# RSD_M1_LED_TURN_LEFT_V2.net
KiCad netlist of a schematic drawn in Altium Designer
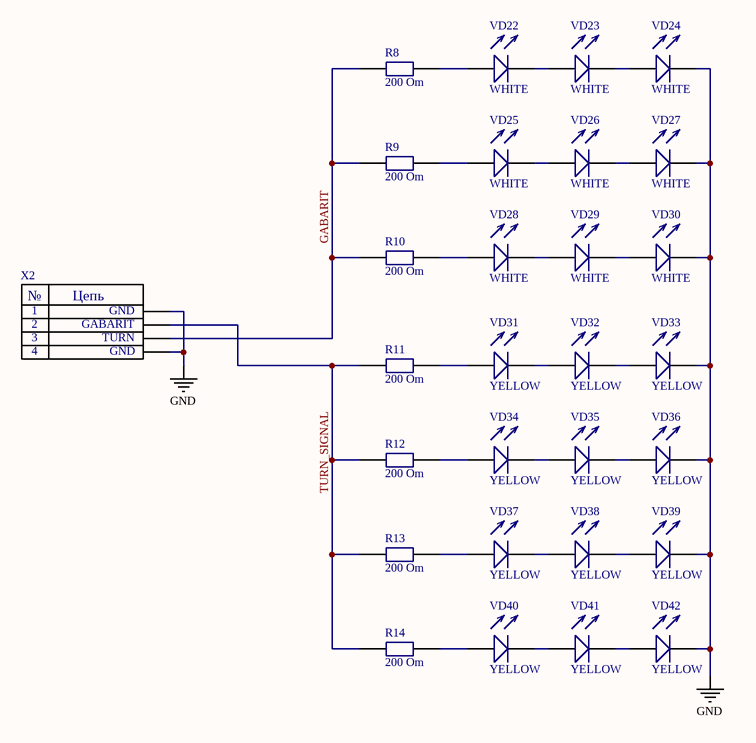
[diagram p0: RSD_M1_LED_TURN_LEFT_V2.SchDoc]

(export (version "E")
  (design (tool "Eeschema 10.0.6"))
  (components
    (comp (ref "R8")
      (value "200 Om")
      (footprint "Res0603")
      (fields (field (name "Comment") "Resistor"))
      (libsource (lib "my_library") (part "Resistor"))
    )
    (comp (ref "R9")
      (value "200 Om")
      (footprint "Res0603")
      (fields (field (name "Comment") "Resistor"))
      (libsource (lib "my_library") (part "Resistor"))
    )
    (comp (ref "R10")
      (value "200 Om")
      (footprint "Res0603")
      (fields (field (name "Comment") "Resistor"))
      (libsource (lib "my_library") (part "Resistor"))
    )
    (comp (ref "R11")
      (value "200 Om")
      (footprint "Res0603")
      (fields (field (name "Comment") "Resistor"))
      (libsource (lib "my_library") (part "Resistor"))
    )
    (comp (ref "R12")
      (value "200 Om")
      (footprint "Res0603")
      (fields (field (name "Comment") "Resistor"))
      (libsource (lib "my_library") (part "Resistor"))
    )
    (comp (ref "R13")
      (value "200 Om")
      (footprint "Res0603")
      (fields (field (name "Comment") "Resistor"))
      (libsource (lib "my_library") (part "Resistor"))
    )
    (comp (ref "R14")
      (value "200 Om")
      (footprint "Res0603")
      (fields (field (name "Comment") "Resistor"))
      (libsource (lib "my_library") (part "Resistor"))
    )
    (comp (ref "VD22")
      (value "WHITE")
      (footprint "3528_LED")
      (fields (field (name "Comment") "LED"))
      (libsource (lib "my_library") (part "LED"))
    )
    (comp (ref "VD23")
      (value "WHITE")
      (footprint "3528_LED")
      (fields (field (name "Comment") "LED"))
      (libsource (lib "my_library") (part "LED"))
    )
    (comp (ref "VD24")
      (value "WHITE")
      (footprint "3528_LED")
      (fields (field (name "Comment") "LED"))
      (libsource (lib "my_library") (part "LED"))
    )
    (comp (ref "VD25")
      (value "WHITE")
      (footprint "3528_LED")
      (fields (field (name "Comment") "LED"))
      (libsource (lib "my_library") (part "LED"))
    )
    (comp (ref "VD26")
      (value "WHITE")
      (footprint "3528_LED")
      (fields (field (name "Comment") "LED"))
      (libsource (lib "my_library") (part "LED"))
    )
    (comp (ref "VD27")
      (value "WHITE")
      (footprint "3528_LED")
      (fields (field (name "Comment") "LED"))
      (libsource (lib "my_library") (part "LED"))
    )
    (comp (ref "VD28")
      (value "WHITE")
      (footprint "3528_LED")
      (fields (field (name "Comment") "LED"))
      (libsource (lib "my_library") (part "LED"))
    )
    (comp (ref "VD29")
      (value "WHITE")
      (footprint "3528_LED")
      (fields (field (name "Comment") "LED"))
      (libsource (lib "my_library") (part "LED"))
    )
    (comp (ref "VD30")
      (value "WHITE")
      (footprint "3528_LED")
      (fields (field (name "Comment") "LED"))
      (libsource (lib "my_library") (part "LED"))
    )
    (comp (ref "VD31")
      (value "YELLOW")
      (footprint "3528_LED")
      (fields (field (name "Comment") "LED"))
      (libsource (lib "my_library") (part "LED"))
    )
    (comp (ref "VD32")
      (value "YELLOW")
      (footprint "3528_LED")
      (fields (field (name "Comment") "LED"))
      (libsource (lib "my_library") (part "LED"))
    )
    (comp (ref "VD33")
      (value "YELLOW")
      (footprint "3528_LED")
      (fields (field (name "Comment") "LED"))
      (libsource (lib "my_library") (part "LED"))
    )
    (comp (ref "VD34")
      (value "YELLOW")
      (footprint "3528_LED")
      (fields (field (name "Comment") "LED"))
      (libsource (lib "my_library") (part "LED"))
    )
    (comp (ref "VD35")
      (value "YELLOW")
      (footprint "3528_LED")
      (fields (field (name "Comment") "LED"))
      (libsource (lib "my_library") (part "LED"))
    )
    (comp (ref "VD36")
      (value "YELLOW")
      (footprint "3528_LED")
      (fields (field (name "Comment") "LED"))
      (libsource (lib "my_library") (part "LED"))
    )
    (comp (ref "VD37")
      (value "YELLOW")
      (footprint "3528_LED")
      (fields (field (name "Comment") "LED"))
      (libsource (lib "my_library") (part "LED"))
    )
    (comp (ref "VD38")
      (value "YELLOW")
      (footprint "3528_LED")
      (fields (field (name "Comment") "LED"))
      (libsource (lib "my_library") (part "LED"))
    )
    (comp (ref "VD39")
      (value "YELLOW")
      (footprint "3528_LED")
      (fields (field (name "Comment") "LED"))
      (libsource (lib "my_library") (part "LED"))
    )
    (comp (ref "VD40")
      (value "YELLOW")
      (footprint "3528_LED")
      (fields (field (name "Comment") "LED"))
      (libsource (lib "my_library") (part "LED"))
    )
    (comp (ref "VD41")
      (value "YELLOW")
      (footprint "3528_LED")
      (fields (field (name "Comment") "LED"))
      (libsource (lib "my_library") (part "LED"))
    )
    (comp (ref "VD42")
      (value "YELLOW")
      (footprint "3528_LED")
      (fields (field (name "Comment") "LED"))
      (libsource (lib "my_library") (part "LED"))
    )
    (comp (ref "X2")
      (value "FPC_connector_4_1")
      (footprint "FPC_4_1")
      (fields
        (field (name "1") "GND")
        (field (name "2") "GABARIT")
        (field (name "3") "TURN")
        (field (name "4") "GND")
      )
      (libsource (lib "my_library") (part "FPC_connector_4_1"))
    )
  )
  (nets
    (net (code "1") (name "/GABARIT") (class "Default")
      (node (ref "R10") (pin "2") (pinfunction "2_2") (pintype "passive"))
      (node (ref "R8") (pin "2") (pinfunction "2_2") (pintype "passive"))
      (node (ref "R9") (pin "2") (pinfunction "2_2") (pintype "passive"))
      (node (ref "X2") (pin "3") (pinfunction "3_3") (pintype "passive"))
    )
    (net (code "2") (name "/TURN_SIGNAL") (class "Default")
      (node (ref "R11") (pin "2") (pinfunction "2_2") (pintype "passive"))
      (node (ref "R12") (pin "2") (pinfunction "2_2") (pintype "passive"))
      (node (ref "R13") (pin "2") (pinfunction "2_2") (pintype "passive"))
      (node (ref "R14") (pin "2") (pinfunction "2_2") (pintype "passive"))
      (node (ref "X2") (pin "2") (pinfunction "2_2") (pintype "passive"))
    )
    (net (code "3") (name "GND") (class "Default")
      (node (ref "VD24") (pin "1") (pinfunction "1_1") (pintype "passive"))
      (node (ref "VD27") (pin "1") (pinfunction "1_1") (pintype "passive"))
      (node (ref "VD30") (pin "1") (pinfunction "1_1") (pintype "passive"))
      (node (ref "VD33") (pin "1") (pinfunction "1_1") (pintype "passive"))
      (node (ref "VD36") (pin "1") (pinfunction "1_1") (pintype "passive"))
      (node (ref "VD39") (pin "1") (pinfunction "1_1") (pintype "passive"))
      (node (ref "VD42") (pin "1") (pinfunction "1_1") (pintype "passive"))
      (node (ref "X2") (pin "1") (pinfunction "1_1") (pintype "passive"))
      (node (ref "X2") (pin "4") (pinfunction "4_4") (pintype "passive"))
    )
    (net (code "4") (name "Net-(R8-Pad1)") (class "Default")
      (node (ref "R8") (pin "1") (pinfunction "1_1") (pintype "passive"))
      (node (ref "VD22") (pin "2") (pinfunction "2_2") (pintype "passive"))
    )
    (net (code "5") (name "Net-(R9-Pad1)") (class "Default")
      (node (ref "R9") (pin "1") (pinfunction "1_1") (pintype "passive"))
      (node (ref "VD25") (pin "2") (pinfunction "2_2") (pintype "passive"))
    )
    (net (code "6") (name "Net-(R10-Pad1)") (class "Default")
      (node (ref "R10") (pin "1") (pinfunction "1_1") (pintype "passive"))
      (node (ref "VD28") (pin "2") (pinfunction "2_2") (pintype "passive"))
    )
    (net (code "7") (name "Net-(R11-Pad1)") (class "Default")
      (node (ref "R11") (pin "1") (pinfunction "1_1") (pintype "passive"))
      (node (ref "VD31") (pin "2") (pinfunction "2_2") (pintype "passive"))
    )
    (net (code "8") (name "Net-(R12-Pad1)") (class "Default")
      (node (ref "R12") (pin "1") (pinfunction "1_1") (pintype "passive"))
      (node (ref "VD34") (pin "2") (pinfunction "2_2") (pintype "passive"))
    )
    (net (code "9") (name "Net-(R13-Pad1)") (class "Default")
      (node (ref "R13") (pin "1") (pinfunction "1_1") (pintype "passive"))
      (node (ref "VD37") (pin "2") (pinfunction "2_2") (pintype "passive"))
    )
    (net (code "10") (name "Net-(R14-Pad1)") (class "Default")
      (node (ref "R14") (pin "1") (pinfunction "1_1") (pintype "passive"))
      (node (ref "VD40") (pin "2") (pinfunction "2_2") (pintype "passive"))
    )
    (net (code "11") (name "Net-(VD22-Pad1)") (class "Default")
      (node (ref "VD22") (pin "1") (pinfunction "1_1") (pintype "passive"))
      (node (ref "VD23") (pin "2") (pinfunction "2_2") (pintype "passive"))
    )
    (net (code "12") (name "Net-(VD23-Pad1)") (class "Default")
      (node (ref "VD23") (pin "1") (pinfunction "1_1") (pintype "passive"))
      (node (ref "VD24") (pin "2") (pinfunction "2_2") (pintype "passive"))
    )
    (net (code "13") (name "Net-(VD25-Pad1)") (class "Default")
      (node (ref "VD25") (pin "1") (pinfunction "1_1") (pintype "passive"))
      (node (ref "VD26") (pin "2") (pinfunction "2_2") (pintype "passive"))
    )
    (net (code "14") (name "Net-(VD26-Pad1)") (class "Default")
      (node (ref "VD26") (pin "1") (pinfunction "1_1") (pintype "passive"))
      (node (ref "VD27") (pin "2") (pinfunction "2_2") (pintype "passive"))
    )
    (net (code "15") (name "Net-(VD28-Pad1)") (class "Default")
      (node (ref "VD28") (pin "1") (pinfunction "1_1") (pintype "passive"))
      (node (ref "VD29") (pin "2") (pinfunction "2_2") (pintype "passive"))
    )
    (net (code "16") (name "Net-(VD29-Pad1)") (class "Default")
      (node (ref "VD29") (pin "1") (pinfunction "1_1") (pintype "passive"))
      (node (ref "VD30") (pin "2") (pinfunction "2_2") (pintype "passive"))
    )
    (net (code "17") (name "Net-(VD31-Pad1)") (class "Default")
      (node (ref "VD31") (pin "1") (pinfunction "1_1") (pintype "passive"))
      (node (ref "VD32") (pin "2") (pinfunction "2_2") (pintype "passive"))
    )
    (net (code "18") (name "Net-(VD32-Pad1)") (class "Default")
      (node (ref "VD32") (pin "1") (pinfunction "1_1") (pintype "passive"))
      (node (ref "VD33") (pin "2") (pinfunction "2_2") (pintype "passive"))
    )
    (net (code "19") (name "Net-(VD34-Pad1)") (class "Default")
      (node (ref "VD34") (pin "1") (pinfunction "1_1") (pintype "passive"))
      (node (ref "VD35") (pin "2") (pinfunction "2_2") (pintype "passive"))
    )
    (net (code "20") (name "Net-(VD35-Pad1)") (class "Default")
      (node (ref "VD35") (pin "1") (pinfunction "1_1") (pintype "passive"))
      (node (ref "VD36") (pin "2") (pinfunction "2_2") (pintype "passive"))
    )
    (net (code "21") (name "Net-(VD37-Pad1)") (class "Default")
      (node (ref "VD37") (pin "1") (pinfunction "1_1") (pintype "passive"))
      (node (ref "VD38") (pin "2") (pinfunction "2_2") (pintype "passive"))
    )
    (net (code "22") (name "Net-(VD38-Pad1)") (class "Default")
      (node (ref "VD38") (pin "1") (pinfunction "1_1") (pintype "passive"))
      (node (ref "VD39") (pin "2") (pinfunction "2_2") (pintype "passive"))
    )
    (net (code "23") (name "Net-(VD40-Pad1)") (class "Default")
      (node (ref "VD40") (pin "1") (pinfunction "1_1") (pintype "passive"))
      (node (ref "VD41") (pin "2") (pinfunction "2_2") (pintype "passive"))
    )
    (net (code "24") (name "Net-(VD41-Pad1)") (class "Default")
      (node (ref "VD41") (pin "1") (pinfunction "1_1") (pintype "passive"))
      (node (ref "VD42") (pin "2") (pinfunction "2_2") (pintype "passive"))
    )
  )
)
